# controlador.net
KiCad netlist of a schematic drawn in EAGLE
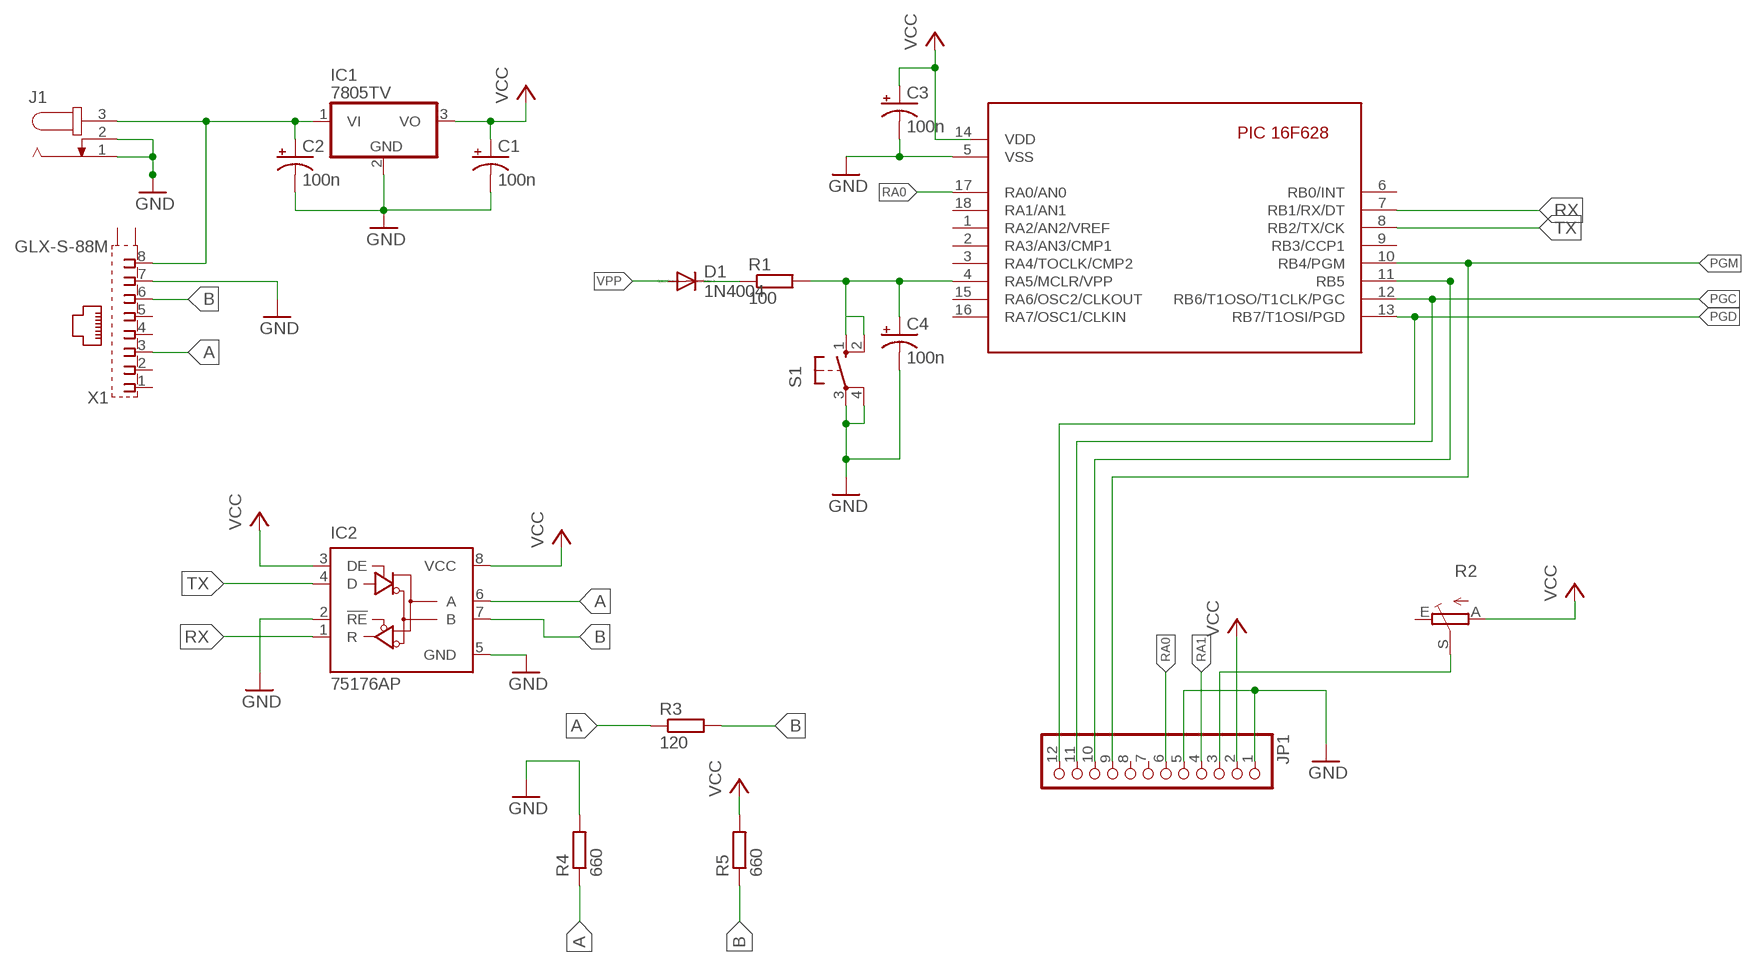
[diagram p0: schematic, sheet 1]

(export (version "E")
  (design (tool "Eeschema 10.0.6"))
  (components
    (comp (ref "C1")
      (value "100n")
      (footprint "eagle-import:E2,5-5")
      (libsource (lib "eagle-import") (part "CPOL-USE2.5-5"))
    )
    (comp (ref "C2")
      (value "100n")
      (footprint "eagle-import:E2,5-5")
      (libsource (lib "eagle-import") (part "CPOL-USE2.5-5"))
    )
    (comp (ref "C3")
      (value "100n")
      (footprint "eagle-import:E2,5-5")
      (libsource (lib "eagle-import") (part "CPOL-USE2.5-5"))
    )
    (comp (ref "C4")
      (value "100n")
      (footprint "eagle-import:E2,5-5")
      (libsource (lib "eagle-import") (part "CPOL-USE2.5-5"))
    )
    (comp (ref "D1")
      (value "1N4004")
      (footprint "eagle-import:DO41-10")
      (libsource (lib "eagle-import") (part "1N4004"))
    )
    (comp (ref "IC1")
      (value "7805TV")
      (footprint "eagle-import:TO220V")
      (libsource (lib "eagle-import") (part "78TV05"))
    )
    (comp (ref "IC2")
      (value "75176AP")
      (footprint "eagle-import:DIL08")
      (libsource (lib "eagle-import") (part "75176AP"))
    )
    (comp (ref "J1")
      (value "JACK-PLUG1")
      (footprint "eagle-import:SPC4078")
      (libsource (lib "eagle-import") (part "JACK-PLUG1"))
    )
    (comp (ref "JP1")
      (value "PINHD-1X12")
      (footprint "eagle-import:1X12")
      (libsource (lib "eagle-import") (part "PINHD-1X12"))
    )
    (comp (ref "R1")
      (value "100")
      (footprint "eagle-import:0204_7")
      (libsource (lib "eagle-import") (part "R-EU_0204/7"))
    )
    (comp (ref "R2")
      (value "TRIM_EU-B25P")
      (footprint "eagle-import:B25P")
      (libsource (lib "eagle-import") (part "TRIM_EU-B25P"))
    )
    (comp (ref "R3")
      (value "120")
      (footprint "eagle-import:0204_7")
      (libsource (lib "eagle-import") (part "R-EU_0204/7"))
    )
    (comp (ref "R4")
      (value "660")
      (footprint "eagle-import:0204_7")
      (libsource (lib "eagle-import") (part "R-EU_0204/7"))
    )
    (comp (ref "R5")
      (value "660")
      (footprint "eagle-import:0204_7")
      (libsource (lib "eagle-import") (part "R-EU_0204/7"))
    )
    (comp (ref "S1")
      (value "10-XX")
      (footprint "eagle-import:B3F-10XX")
      (fields (field (name "MPN") "B3F-1000"))
      (libsource (lib "eagle-import") (part "10-XX"))
    )
    (comp (ref "U$1")
      (value "16F628")
      (footprint "eagle-import:PIC16F628-18-LEAD-PDIP")
      (libsource (lib "eagle-import") (part "16F628"))
    )
    (comp (ref "X1")
      (value "GLX-S-88M")
      (footprint "eagle-import:GLX-S-88M")
      (libsource (lib "eagle-import") (part "GLX-S-88M"))
    )
  )
  (nets
    (net (code "1") (name "A") (class "Default")
      (node (ref "IC2") (pin "6") (pinfunction "A_6") (pintype "output"))
      (node (ref "R3") (pin "1") (pinfunction "1_1") (pintype "passive"))
      (node (ref "R4") (pin "1") (pinfunction "1_1") (pintype "passive"))
      (node (ref "X1") (pin "3") (pinfunction "3_3") (pintype "passive"))
    )
    (net (code "2") (name "B") (class "Default")
      (node (ref "IC2") (pin "7") (pinfunction "B_7") (pintype "output"))
      (node (ref "R3") (pin "2") (pinfunction "2_2") (pintype "passive"))
      (node (ref "R5") (pin "1") (pinfunction "1_1") (pintype "passive"))
      (node (ref "X1") (pin "6") (pinfunction "6_6") (pintype "passive"))
    )
    (net (code "3") (name "GND") (class "Default")
      (node (ref "C1") (pin "-") (pinfunction "-_-") (pintype "passive"))
      (node (ref "C2") (pin "-") (pinfunction "-_-") (pintype "passive"))
      (node (ref "C3") (pin "-") (pinfunction "-_-") (pintype "passive"))
      (node (ref "C4") (pin "-") (pinfunction "-_-") (pintype "passive"))
      (node (ref "IC1") (pin "2") (pinfunction "GND_2") (pintype "passive"))
      (node (ref "IC2") (pin "2") (pinfunction "~{RE}_2") (pintype "input"))
      (node (ref "IC2") (pin "5") (pinfunction "GND_5") (pintype "power_in"))
      (node (ref "J1") (pin "1") (pinfunction "1_1") (pintype "passive"))
      (node (ref "J1") (pin "2") (pinfunction "2_2") (pintype "passive"))
      (node (ref "JP1") (pin "1") (pinfunction "1_1") (pintype "passive"))
      (node (ref "JP1") (pin "5") (pinfunction "5_5") (pintype "passive"))
      (node (ref "R4") (pin "2") (pinfunction "2_2") (pintype "passive"))
      (node (ref "S1") (pin "3") (pinfunction "P_3") (pintype "passive"))
      (node (ref "S1") (pin "4") (pinfunction "P1_4") (pintype "passive"))
      (node (ref "U$1") (pin "5") (pinfunction "VSS_5") (pintype "input"))
      (node (ref "X1") (pin "7") (pinfunction "7_7") (pintype "passive"))
    )
    (net (code "4") (name "Net-(D1-PadC)") (class "Default")
      (node (ref "D1") (pin "C") (pinfunction "C_C") (pintype "passive"))
      (node (ref "R1") (pin "1") (pinfunction "1_1") (pintype "passive"))
    )
    (net (code "5") (name "Net-(IC1-VI)") (class "Default")
      (node (ref "C2") (pin "+") (pinfunction "+_+") (pintype "passive"))
      (node (ref "IC1") (pin "1") (pinfunction "VI_1") (pintype "input"))
      (node (ref "J1") (pin "3") (pinfunction "3_3") (pintype "passive"))
      (node (ref "X1") (pin "8") (pinfunction "8_8") (pintype "passive"))
    )
    (net (code "6") (name "Net-(JP1-Pad3)") (class "Default")
      (node (ref "JP1") (pin "3") (pinfunction "3_3") (pintype "passive"))
      (node (ref "R2") (pin "S") (pinfunction "S_S") (pintype "passive"))
    )
    (net (code "7") (name "Net-(U$1-RB5)") (class "Default")
      (node (ref "JP1") (pin "10") (pinfunction "10_10") (pintype "passive"))
      (node (ref "U$1") (pin "11") (pinfunction "RB5_11") (pintype "bidirectional"))
    )
    (net (code "8") (name "PGC") (class "Default")
      (node (ref "JP1") (pin "11") (pinfunction "11_11") (pintype "passive"))
      (node (ref "U$1") (pin "12") (pinfunction "RB6/T1OSO/T1CLK/PGC_12") (pintype "bidirectional"))
    )
    (net (code "9") (name "PGD") (class "Default")
      (node (ref "JP1") (pin "12") (pinfunction "12_12") (pintype "passive"))
      (node (ref "U$1") (pin "13") (pinfunction "RB7/T1OSI/PGD_13") (pintype "bidirectional"))
    )
    (net (code "10") (name "PGM") (class "Default")
      (node (ref "JP1") (pin "9") (pinfunction "9_9") (pintype "passive"))
      (node (ref "U$1") (pin "10") (pinfunction "RB4/PGM_10") (pintype "bidirectional"))
    )
    (net (code "11") (name "RA0") (class "Default")
      (node (ref "JP1") (pin "6") (pinfunction "6_6") (pintype "passive"))
      (node (ref "U$1") (pin "17") (pinfunction "RA0/AN0_17") (pintype "bidirectional"))
    )
    (net (code "12") (name "RA1") (class "Default")
      (node (ref "JP1") (pin "4") (pinfunction "4_4") (pintype "passive"))
    )
    (net (code "13") (name "RX") (class "Default")
      (node (ref "IC2") (pin "1") (pinfunction "R_1") (pintype "input"))
      (node (ref "U$1") (pin "7") (pinfunction "RB1/RX/DT_7") (pintype "bidirectional"))
    )
    (net (code "14") (name "TX") (class "Default")
      (node (ref "IC2") (pin "4") (pinfunction "D_4") (pintype "input"))
      (node (ref "U$1") (pin "8") (pinfunction "RB2/TX/CK_8") (pintype "bidirectional"))
    )
    (net (code "15") (name "VCC") (class "Default")
      (node (ref "C1") (pin "+") (pinfunction "+_+") (pintype "passive"))
      (node (ref "C3") (pin "+") (pinfunction "+_+") (pintype "passive"))
      (node (ref "IC1") (pin "3") (pinfunction "VO_3") (pintype "passive"))
      (node (ref "IC2") (pin "3") (pinfunction "DE_3") (pintype "input"))
      (node (ref "IC2") (pin "8") (pinfunction "VCC_8") (pintype "power_in"))
      (node (ref "JP1") (pin "2") (pinfunction "2_2") (pintype "passive"))
      (node (ref "R2") (pin "A") (pinfunction "A_A") (pintype "passive"))
      (node (ref "R5") (pin "2") (pinfunction "2_2") (pintype "passive"))
      (node (ref "U$1") (pin "14") (pinfunction "VDD_14") (pintype "input"))
    )
    (net (code "16") (name "VPP") (class "Default")
      (node (ref "C4") (pin "+") (pinfunction "+_+") (pintype "passive"))
      (node (ref "D1") (pin "A") (pinfunction "A_A") (pintype "passive"))
      (node (ref "R1") (pin "2") (pinfunction "2_2") (pintype "passive"))
      (node (ref "S1") (pin "1") (pinfunction "S_1") (pintype "passive"))
      (node (ref "S1") (pin "2") (pinfunction "S1_2") (pintype "passive"))
      (node (ref "U$1") (pin "4") (pinfunction "RA5/MCLR/VPP_4") (pintype "bidirectional"))
    )
    (net (code "17") (name "unconnected-(JP1-Pad7)") (class "Default")
      (node (ref "JP1") (pin "7") (pinfunction "7_7") (pintype "passive"))
    )
    (net (code "18") (name "unconnected-(JP1-Pad8)") (class "Default")
      (node (ref "JP1") (pin "8") (pinfunction "8_8") (pintype "passive"))
    )
    (net (code "19") (name "unconnected-(R2-PadE)") (class "Default")
      (node (ref "R2") (pin "E") (pinfunction "E_E") (pintype "passive"))
    )
    (net (code "20") (name "unconnected-(U$1-RA1{slash}AN1-Pad18)") (class "Default")
      (node (ref "U$1") (pin "18") (pinfunction "RA1/AN1_18") (pintype "bidirectional"))
    )
    (net (code "21") (name "unconnected-(U$1-RA2{slash}AN2{slash}VREF-Pad1)") (class "Default")
      (node (ref "U$1") (pin "1") (pinfunction "RA2/AN2/VREF_1") (pintype "bidirectional"))
    )
    (net (code "22") (name "unconnected-(U$1-RA3{slash}AN3{slash}CMP1-Pad2)") (class "Default")
      (node (ref "U$1") (pin "2") (pinfunction "RA3/AN3/CMP1_2") (pintype "bidirectional"))
    )
    (net (code "23") (name "unconnected-(U$1-RA4{slash}TOCLK{slash}CMP2-Pad3)") (class "Default")
      (node (ref "U$1") (pin "3") (pinfunction "RA4/TOCLK/CMP2_3") (pintype "bidirectional"))
    )
    (net (code "24") (name "unconnected-(U$1-RA6{slash}OSC2{slash}CLKOUT-Pad15)") (class "Default")
      (node (ref "U$1") (pin "15") (pinfunction "RA6/OSC2/CLKOUT_15") (pintype "bidirectional"))
    )
    (net (code "25") (name "unconnected-(U$1-RA7{slash}OSC1{slash}CLKIN-Pad16)") (class "Default")
      (node (ref "U$1") (pin "16") (pinfunction "RA7/OSC1/CLKIN_16") (pintype "bidirectional"))
    )
    (net (code "26") (name "unconnected-(U$1-RB0{slash}INT-Pad6)") (class "Default")
      (node (ref "U$1") (pin "6") (pinfunction "RB0/INT_6") (pintype "bidirectional"))
    )
    (net (code "27") (name "unconnected-(U$1-RB3{slash}CCP1-Pad9)") (class "Default")
      (node (ref "U$1") (pin "9") (pinfunction "RB3/CCP1_9") (pintype "bidirectional"))
    )
    (net (code "28") (name "unconnected-(X1-Pad1)") (class "Default")
      (node (ref "X1") (pin "1") (pinfunction "1_1") (pintype "passive"))
    )
    (net (code "29") (name "unconnected-(X1-Pad2)") (class "Default")
      (node (ref "X1") (pin "2") (pinfunction "2_2") (pintype "passive"))
    )
    (net (code "30") (name "unconnected-(X1-Pad4)") (class "Default")
      (node (ref "X1") (pin "4") (pinfunction "4_4") (pintype "passive"))
    )
    (net (code "31") (name "unconnected-(X1-Pad5)") (class "Default")
      (node (ref "X1") (pin "5") (pinfunction "5_5") (pintype "passive"))
    )
    (net (code "32") (name "unconnected-(X1-PadS1)") (class "Default")
      (node (ref "X1") (pin "S1") (pinfunction "S1_S1") (pintype "passive"))
    )
    (net (code "33") (name "unconnected-(X1-PadS2)") (class "Default")
      (node (ref "X1") (pin "S2") (pinfunction "S2_S2") (pintype "passive"))
    )
  )
)
